# header_connect_class_II.net
KiCad netlist of a schematic drawn in Altium Designer
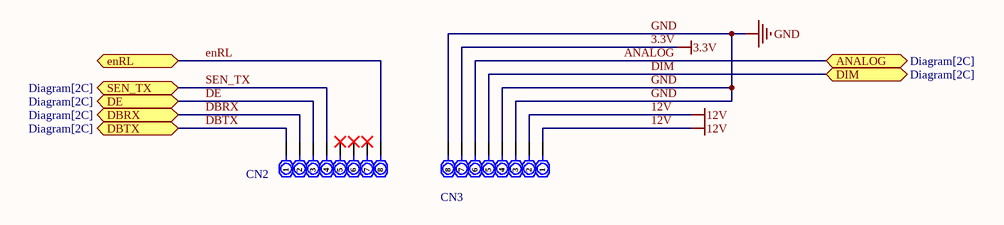
[diagram p0: header_connect_class_II.SchDoc]

(export (version "E")
  (design (tool "Eeschema 10.0.6"))
  (components
    (comp (ref "CN2")
      (value "LEFT")
      (footprint "CON.HDR1X8")
      (description "Header 1x5")
      (fields (field (name "PUBLISHER") "Hoang Nguyen"))
      (libsource (lib "VPMyLibrary") (part "CON.HDR1x8"))
    )
    (comp (ref "CN3")
      (value "RIGHT")
      (footprint "CON.HDR1X8")
      (description "Header 1x5")
      (fields (field (name "PUBLISHER") "Hoang Nguyen"))
      (libsource (lib "VPMyLibrary") (part "CON.HDR1x8"))
    )
  )
  (nets
    (net (code "1") (name "/ANALOG") (class "Default")
      (node (ref "CN3") (pin "6") (pinfunction "6_6") (pintype "passive"))
    )
    (net (code "2") (name "/DBRX") (class "Default")
      (node (ref "CN2") (pin "2") (pinfunction "2_2") (pintype "passive"))
    )
    (net (code "3") (name "/DBTX") (class "Default")
      (node (ref "CN2") (pin "1") (pinfunction "1_1") (pintype "passive"))
    )
    (net (code "4") (name "/DE") (class "Default")
      (node (ref "CN2") (pin "3") (pinfunction "3_3") (pintype "passive"))
    )
    (net (code "5") (name "/DIM") (class "Default")
      (node (ref "CN3") (pin "5") (pinfunction "5_5") (pintype "passive"))
    )
    (net (code "6") (name "/SEN_TX") (class "Default")
      (node (ref "CN2") (pin "4") (pinfunction "4_4") (pintype "passive"))
    )
    (net (code "7") (name "/enRL") (class "Default")
      (node (ref "CN2") (pin "8") (pinfunction "8_8") (pintype "passive"))
    )
    (net (code "8") (name "3.3V") (class "Default")
      (node (ref "CN3") (pin "7") (pinfunction "7_7") (pintype "passive"))
    )
    (net (code "9") (name "12V") (class "Default")
      (node (ref "CN3") (pin "1") (pinfunction "1_1") (pintype "passive"))
      (node (ref "CN3") (pin "2") (pinfunction "2_2") (pintype "passive"))
    )
    (net (code "10") (name "GND") (class "Default")
      (node (ref "CN3") (pin "3") (pinfunction "3_3") (pintype "passive"))
      (node (ref "CN3") (pin "4") (pinfunction "4_4") (pintype "passive"))
      (node (ref "CN3") (pin "8") (pinfunction "8_8") (pintype "passive"))
    )
    (net (code "11") (name "unconnected-(CN2-Pad5)") (class "Default")
      (node (ref "CN2") (pin "5") (pinfunction "5_5") (pintype "passive+no_connect"))
    )
    (net (code "12") (name "unconnected-(CN2-Pad6)") (class "Default")
      (node (ref "CN2") (pin "6") (pinfunction "6_6") (pintype "passive+no_connect"))
    )
    (net (code "13") (name "unconnected-(CN2-Pad7)") (class "Default")
      (node (ref "CN2") (pin "7") (pinfunction "7_7") (pintype "passive+no_connect"))
    )
  )
)
